# Sheet4.net
KiCad netlist of a schematic drawn in Altium Designer
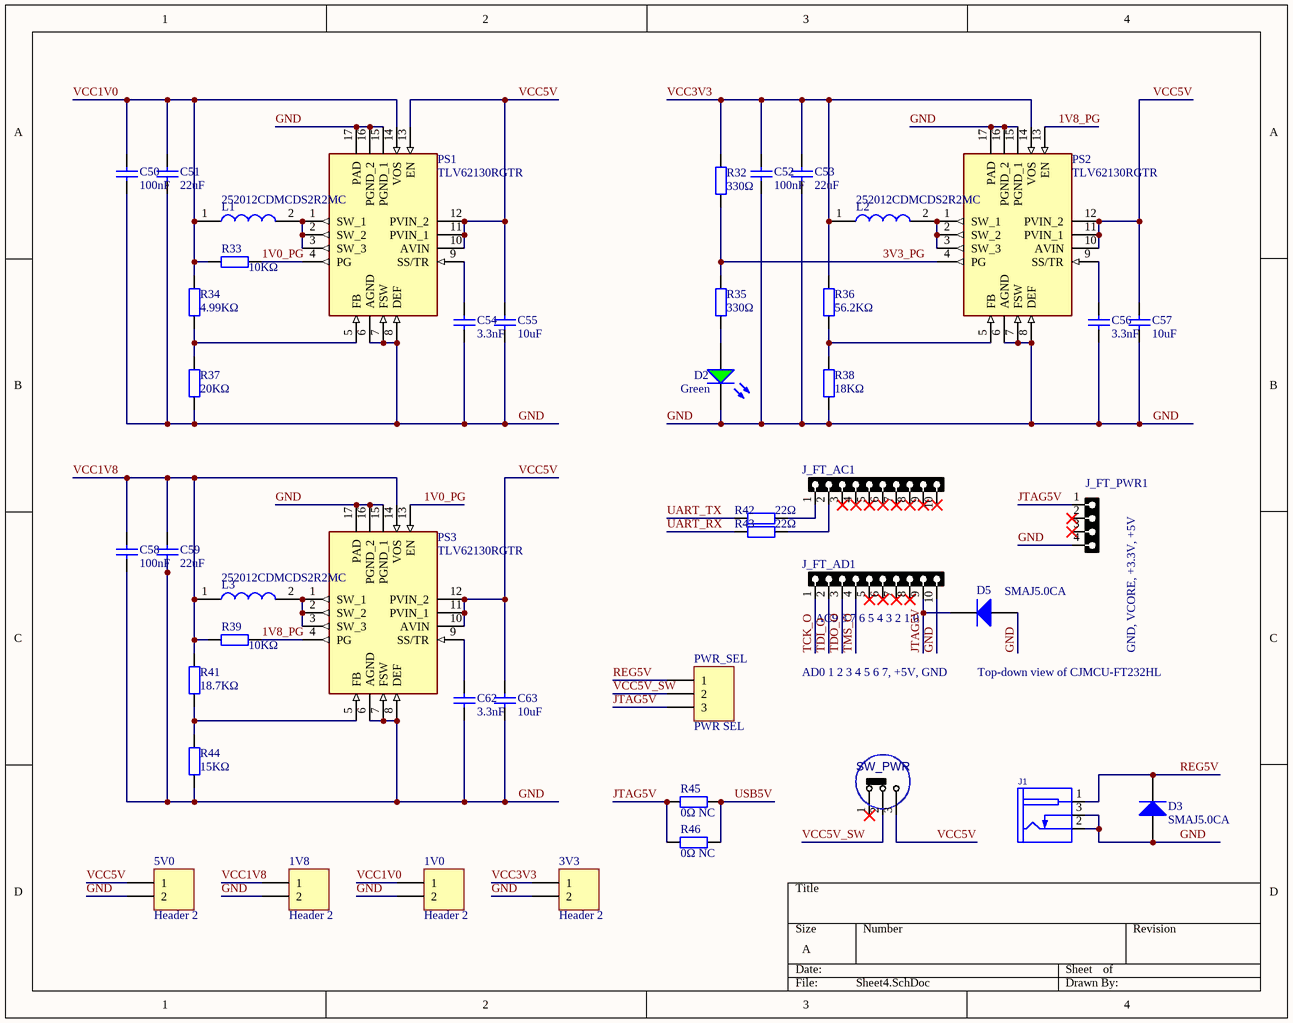
[diagram p0: Sheet4.SchDoc]

(export (version "E")
  (design (tool "Eeschema 10.0.6"))
  (components
    (comp (ref "1V0")
      (value "Header 2")
      (footprint "HDR1X2")
      (description "Header, 2-Pin")
      (fields (field (name "PUBLISHER") "Altium Limited"))
      (libsource (lib "Miscellaneous Connectors") (part "Header 2"))
    )
    (comp (ref "1V8")
      (value "Header 2")
      (footprint "HDR1X2")
      (description "Header, 2-Pin")
      (fields (field (name "PUBLISHER") "Altium Limited"))
      (libsource (lib "Miscellaneous Connectors") (part "Header 2"))
    )
    (comp (ref "3V3")
      (value "Header 2")
      (footprint "HDR1X2")
      (description "Header, 2-Pin")
      (fields (field (name "PUBLISHER") "Altium Limited"))
      (libsource (lib "Miscellaneous Connectors") (part "Header 2"))
    )
    (comp (ref "5V0")
      (value "Header 2")
      (footprint "HDR1X2")
      (description "Header, 2-Pin")
      (fields (field (name "PUBLISHER") "Altium Limited"))
      (libsource (lib "Miscellaneous Connectors") (part "Header 2"))
    )
    (comp (ref "C50")
      (value "100nF")
      (footprint "1206_C")
      (description "贴片电容")
      (libsource (lib "Cap") (part "1206 100nF (104) 10% 50V"))
    )
    (comp (ref "C51")
      (value "22uF")
      (footprint "0805_C")
      (description "贴片电容")
      (libsource (lib "Cap") (part "0805 22uF (226) 20% 25V"))
    )
    (comp (ref "C52")
      (value "100nF")
      (footprint "1206_C")
      (description "贴片电容")
      (libsource (lib "Cap") (part "1206 100nF (104) 10% 50V"))
    )
    (comp (ref "C53")
      (value "22uF")
      (footprint "0805_C")
      (description "贴片电容")
      (libsource (lib "Cap") (part "0805 22uF (226) 20% 25V"))
    )
    (comp (ref "C54")
      (value "3.3nF")
      (footprint "0805_C")
      (description "贴片电容")
      (libsource (lib "Cap") (part "0805 3.3nF (332) 10% 50V"))
    )
    (comp (ref "C55")
      (value "10uF")
      (footprint "1206_C")
      (description "贴片电容")
      (libsource (lib "Cap") (part "1206 10uF (106) 10% 50V"))
    )
    (comp (ref "C56")
      (value "3.3nF")
      (footprint "0805_C")
      (description "贴片电容")
      (libsource (lib "Cap") (part "0805 3.3nF (332) 10% 50V"))
    )
    (comp (ref "C57")
      (value "10uF")
      (footprint "1206_C")
      (description "贴片电容")
      (libsource (lib "Cap") (part "1206 10uF (106) 10% 50V"))
    )
    (comp (ref "C58")
      (value "100nF")
      (footprint "1206_C")
      (description "贴片电容")
      (libsource (lib "Cap") (part "1206 100nF (104) 10% 50V"))
    )
    (comp (ref "C59")
      (value "22uF")
      (footprint "0805_C")
      (description "贴片电容")
      (libsource (lib "Cap") (part "0805 22uF (226) 20% 25V"))
    )
    (comp (ref "C62")
      (value "3.3nF")
      (footprint "0805_C")
      (description "贴片电容")
      (libsource (lib "Cap") (part "0805 3.3nF (332) 10% 50V"))
    )
    (comp (ref "C63")
      (value "10uF")
      (footprint "1206_C")
      (description "贴片电容")
      (libsource (lib "Cap") (part "1206 10uF (106) 10% 50V"))
    )
    (comp (ref "D2")
      (value "Green")
      (footprint "0805_LED_S1")
      (description "发光二极管")
      (libsource (lib "LED") (part "0805 翠绿"))
    )
    (comp (ref "D3")
      (value "SMAJ5.0CA")
      (footprint "SMA(DO-214AC)_S1")
      (description "二极管 TVS")
      (libsource (lib "Diode") (part "SMA(DO-214AC) SS210"))
    )
    (comp (ref "D5")
      (value "SMAJ5.0CA")
      (footprint "SMA(DO-214AC)_S1")
      (description "二极管 TVS")
      (libsource (lib "Diode") (part "SMA(DO-214AC) SS210"))
    )
    (comp (ref "J1")
      (value "DC_POWER_JACK")
      (footprint "JAC_PWR2MM")
      (description "CONN, PWR JACK DC, PLUG DIAM 2.0MM RA THD")
      (fields
        (field (name "MANF") "CUI STACK")
        (field (name "MANF_P#") "PJ-202A, PJ-002AH, PJ-102AH, KLDX-0202")
      )
      (libsource (lib "Connector Power") (part "CONN_PWR_JACK2MM"))
    )
    (comp (ref "J_FT_AC1")
      (value "HDRF10")
      (footprint "HDR_F_1X10")
      (description "CONN, HEADER, Female, pitch: 2.54mm, 10POS")
      (libsource (lib "Connector Header 254") (part "HDR_F_1X10"))
    )
    (comp (ref "J_FT_AD1")
      (value "HDRF10")
      (footprint "HDR_F_1X10")
      (description "CONN, HEADER, Female, pitch: 2.54mm, 10POS")
      (libsource (lib "Connector Header 254") (part "HDR_F_1X10"))
    )
    (comp (ref "J_FT_PWR1")
      (value "HDRF4")
      (footprint "HDR_F_1X4")
      (description "CONN, HEADER, Female, pitch: 2.54mm, 4POS")
      (libsource (lib "Connector Header 254") (part "HDR_F_1X4"))
    )
    (comp (ref "L1")
      (value "252012CDMCDS2R2MC")
      (footprint "SamacSys:INDPM2520X120N")
      (description "Inductor")
      (fields (field (name "MANUFACTURER_PART_NUMBER") "252012CDMCDS‐2R2MC"))
      (libsource (lib "*") (part "252012CDMCDS2R2MC"))
    )
    (comp (ref "L2")
      (value "252012CDMCDS2R2MC")
      (footprint "SamacSys:INDPM2520X120N")
      (description "Inductor")
      (fields (field (name "MANUFACTURER_PART_NUMBER") "252012CDMCDS‐2R2MC"))
      (libsource (lib "*") (part "252012CDMCDS2R2MC"))
    )
    (comp (ref "L3")
      (value "252012CDMCDS2R2MC")
      (footprint "SamacSys:INDPM2520X120N")
      (description "Inductor")
      (fields (field (name "MANUFACTURER_PART_NUMBER") "252012CDMCDS‐2R2MC"))
      (libsource (lib "*") (part "252012CDMCDS2R2MC"))
    )
    (comp (ref "PS1")
      (value "TLV62130RGTR")
      (footprint "SamacSys:QFN50P300X300X100-17N-D")
      (description "Power Supply")
      (fields (field (name "MOUSER PART NUMBER") "595-TLV62130RGTR"))
      (libsource (lib "*") (part "TLV62130RGTR"))
    )
    (comp (ref "PS2")
      (value "TLV62130RGTR")
      (footprint "SamacSys:QFN50P300X300X100-17N-D")
      (description "Power Supply")
      (fields (field (name "MOUSER PART NUMBER") "595-TLV62130RGTR"))
      (libsource (lib "*") (part "TLV62130RGTR"))
    )
    (comp (ref "PS3")
      (value "TLV62130RGTR")
      (footprint "SamacSys:QFN50P300X300X100-17N-D")
      (description "Power Supply")
      (fields (field (name "MOUSER PART NUMBER") "595-TLV62130RGTR"))
      (libsource (lib "*") (part "TLV62130RGTR"))
    )
    (comp (ref "PWR_SEL")
      (value "PWR SEL")
      (footprint "HDR1X3")
      (description "Header, 3-Pin")
      (fields (field (name "PUBLISHER") "Altium Limited"))
      (libsource (lib "Miscellaneous Connectors") (part "Header 3"))
    )
    (comp (ref "R32")
      (value "330Ω")
      (footprint "0805_R")
      (description "贴片电阻")
      (libsource (lib "RES") (part "0805 330Ω (3300) 1%"))
    )
    (comp (ref "R33")
      (value "10KΩ")
      (footprint "1206_R")
      (description "贴片电阻")
      (libsource (lib "RES") (part "1206 10KΩ (1002) 1%"))
    )
    (comp (ref "R34")
      (value "4.99KΩ")
      (footprint "0805_R")
      (description "贴片电阻")
      (libsource (lib "RES") (part "0805 4.99KΩ (4991) 1%"))
    )
    (comp (ref "R35")
      (value "330Ω")
      (footprint "0805_R")
      (description "贴片电阻")
      (libsource (lib "RES") (part "0805 330Ω (3300) 1%"))
    )
    (comp (ref "R36")
      (value "56.2KΩ")
      (footprint "0805_R")
      (description "贴片电阻 56.2k")
      (libsource (lib "RES") (part "0805 56KΩ (5602) 1%"))
    )
    (comp (ref "R37")
      (value "20KΩ")
      (footprint "0805_R")
      (description "贴片电阻")
      (libsource (lib "RES") (part "0805 20KΩ (2002) 1%"))
    )
    (comp (ref "R38")
      (value "18KΩ")
      (footprint "0805_R")
      (description "贴片电阻")
      (libsource (lib "RES") (part "0805 18KΩ (1802) 1%"))
    )
    (comp (ref "R39")
      (value "10KΩ")
      (footprint "1206_R")
      (description "贴片电阻")
      (libsource (lib "RES") (part "1206 10KΩ (1002) 1%"))
    )
    (comp (ref "R41")
      (value "18.7KΩ")
      (footprint "0805_R")
      (description "贴片电阻 18.7k")
      (libsource (lib "RES") (part "0805 18KΩ (1802) 1%"))
    )
    (comp (ref "R42")
      (value "22Ω")
      (footprint "1206_R")
      (description "贴片电阻")
      (libsource (lib "RES") (part "1206 22Ω (22R0) 1%"))
    )
    (comp (ref "R43")
      (value "22Ω")
      (footprint "1206_R")
      (description "贴片电阻")
      (libsource (lib "RES") (part "1206 22Ω (22R0) 1%"))
    )
    (comp (ref "R44")
      (value "15KΩ")
      (footprint "0805_R")
      (description "贴片电阻")
      (libsource (lib "RES") (part "0805 15KΩ (1502) 1%"))
    )
    (comp (ref "R45")
      (value "0Ω NC")
      (footprint "0805_R")
      (description "贴片电阻")
      (libsource (lib "RES") (part "0805 0Ω (0R0) 1%"))
    )
    (comp (ref "R46")
      (value "0Ω NC")
      (footprint "0805_R")
      (description "贴片电阻")
      (libsource (lib "RES") (part "0805 0Ω (0R0) 1%"))
    )
    (comp (ref "SW_PWR")
      (value "SlideSwitch")
      (footprint "SWSLIDT_SPDT_S_8X4")
      (description "SWITCH, SLIDE, SPDT, 8.6X4.3mm, THD")
      (fields (field (name "MANF") "C&K") (field (name "MANF_PART#") "OS102011MS2QN1"))
      (libsource (lib "Switch Slide") (part "SWSLIDT_SPDT_S_8X4"))
    )
  )
  (nets
    (net (code "1") (name "/1V0_PG") (class "Default")
      (node (ref "PS1") (pin "4") (pinfunction "PG_4") (pintype "output"))
      (node (ref "PS3") (pin "13") (pinfunction "EN_13") (pintype "input"))
      (node (ref "R33") (pin "2") (pinfunction "2_2") (pintype "passive"))
    )
    (net (code "2") (name "/1V8_PG") (class "Default")
      (node (ref "PS2") (pin "13") (pinfunction "EN_13") (pintype "input"))
      (node (ref "PS3") (pin "4") (pinfunction "PG_4") (pintype "output"))
      (node (ref "R39") (pin "2") (pinfunction "2_2") (pintype "passive"))
    )
    (net (code "3") (name "/3V3_PG") (class "Default")
      (node (ref "PS2") (pin "4") (pinfunction "PG_4") (pintype "output"))
      (node (ref "R32") (pin "1") (pinfunction "1_1") (pintype "passive"))
      (node (ref "R35") (pin "2") (pinfunction "2_2") (pintype "passive"))
    )
    (net (code "4") (name "/GND") (class "Default")
      (node (ref "1V0") (pin "2") (pinfunction "2_2") (pintype "passive"))
      (node (ref "1V8") (pin "2") (pinfunction "2_2") (pintype "passive"))
      (node (ref "3V3") (pin "2") (pinfunction "2_2") (pintype "passive"))
      (node (ref "5V0") (pin "2") (pinfunction "2_2") (pintype "passive"))
      (node (ref "C50") (pin "1") (pinfunction "1_1") (pintype "passive"))
      (node (ref "C51") (pin "1") (pinfunction "1_1") (pintype "passive"))
      (node (ref "C52") (pin "1") (pinfunction "1_1") (pintype "passive"))
      (node (ref "C53") (pin "1") (pinfunction "1_1") (pintype "passive"))
      (node (ref "C54") (pin "1") (pinfunction "1_1") (pintype "passive"))
      (node (ref "C55") (pin "1") (pinfunction "1_1") (pintype "passive"))
      (node (ref "C56") (pin "1") (pinfunction "1_1") (pintype "passive"))
      (node (ref "C57") (pin "1") (pinfunction "1_1") (pintype "passive"))
      (node (ref "C58") (pin "1") (pinfunction "1_1") (pintype "passive"))
      (node (ref "C59") (pin "1") (pinfunction "1_1") (pintype "passive"))
      (node (ref "C62") (pin "1") (pinfunction "1_1") (pintype "passive"))
      (node (ref "C63") (pin "1") (pinfunction "1_1") (pintype "passive"))
      (node (ref "D2") (pin "K") (pinfunction "K_K") (pintype "passive"))
      (node (ref "D3") (pin "1") (pinfunction "A_1") (pintype "passive"))
      (node (ref "D5") (pin "1") (pinfunction "A_1") (pintype "passive"))
      (node (ref "J1") (pin "2") (pinfunction "SLEEVE_2") (pintype "power_in"))
      (node (ref "J1") (pin "3") (pinfunction "INSERTION_DET_3") (pintype "power_in"))
      (node (ref "J_FT_AD1") (pin "10") (pinfunction "10_10") (pintype "passive"))
      (node (ref "J_FT_PWR1") (pin "4") (pinfunction "4_4") (pintype "passive"))
      (node (ref "PS1") (pin "15") (pinfunction "PGND_1_15") (pintype "power_in"))
      (node (ref "PS1") (pin "16") (pinfunction "PGND_2_16") (pintype "power_in"))
      (node (ref "PS1") (pin "17") (pinfunction "PAD_17") (pintype "power_in"))
      (node (ref "PS1") (pin "6") (pinfunction "AGND_6") (pintype "power_in"))
      (node (ref "PS1") (pin "7") (pinfunction "FSW_7") (pintype "input"))
      (node (ref "PS1") (pin "8") (pinfunction "DEF_8") (pintype "input"))
      (node (ref "PS2") (pin "15") (pinfunction "PGND_1_15") (pintype "power_in"))
      (node (ref "PS2") (pin "16") (pinfunction "PGND_2_16") (pintype "power_in"))
      (node (ref "PS2") (pin "17") (pinfunction "PAD_17") (pintype "power_in"))
      (node (ref "PS2") (pin "6") (pinfunction "AGND_6") (pintype "power_in"))
      (node (ref "PS2") (pin "7") (pinfunction "FSW_7") (pintype "input"))
      (node (ref "PS2") (pin "8") (pinfunction "DEF_8") (pintype "input"))
      (node (ref "PS3") (pin "15") (pinfunction "PGND_1_15") (pintype "power_in"))
      (node (ref "PS3") (pin "16") (pinfunction "PGND_2_16") (pintype "power_in"))
      (node (ref "PS3") (pin "17") (pinfunction "PAD_17") (pintype "power_in"))
      (node (ref "PS3") (pin "6") (pinfunction "AGND_6") (pintype "power_in"))
      (node (ref "PS3") (pin "7") (pinfunction "FSW_7") (pintype "input"))
      (node (ref "PS3") (pin "8") (pinfunction "DEF_8") (pintype "input"))
      (node (ref "R37") (pin "1") (pinfunction "1_1") (pintype "passive"))
      (node (ref "R38") (pin "1") (pinfunction "1_1") (pintype "passive"))
      (node (ref "R44") (pin "1") (pinfunction "1_1") (pintype "passive"))
    )
    (net (code "5") (name "/JTAG5V") (class "Default")
      (node (ref "D5") (pin "2") (pinfunction "K_2") (pintype "passive"))
      (node (ref "J_FT_AD1") (pin "9") (pinfunction "9_9") (pintype "passive"))
      (node (ref "J_FT_PWR1") (pin "1") (pinfunction "1_1") (pintype "passive"))
      (node (ref "PWR_SEL") (pin "3") (pinfunction "3_3") (pintype "passive"))
      (node (ref "R45") (pin "1") (pinfunction "1_1") (pintype "passive"))
      (node (ref "R46") (pin "1") (pinfunction "1_1") (pintype "passive"))
    )
    (net (code "6") (name "/REG5V") (class "Default")
      (node (ref "D3") (pin "2") (pinfunction "K_2") (pintype "passive"))
      (node (ref "J1") (pin "1") (pinfunction "TIP_1") (pintype "power_in"))
      (node (ref "PWR_SEL") (pin "1") (pinfunction "1_1") (pintype "passive"))
    )
    (net (code "7") (name "/TCK_O") (class "Default")
      (node (ref "J_FT_AD1") (pin "1") (pinfunction "1_1") (pintype "passive"))
    )
    (net (code "8") (name "/TDI_O") (class "Default")
      (node (ref "J_FT_AD1") (pin "2") (pinfunction "2_2") (pintype "passive"))
    )
    (net (code "9") (name "/TDO_O") (class "Default")
      (node (ref "J_FT_AD1") (pin "3") (pinfunction "3_3") (pintype "passive"))
    )
    (net (code "10") (name "/TMS_O") (class "Default")
      (node (ref "J_FT_AD1") (pin "4") (pinfunction "4_4") (pintype "passive"))
    )
    (net (code "11") (name "/UART_RX") (class "Default")
      (node (ref "R43") (pin "1") (pinfunction "1_1") (pintype "passive"))
    )
    (net (code "12") (name "/UART_TX") (class "Default")
      (node (ref "R42") (pin "1") (pinfunction "1_1") (pintype "passive"))
    )
    (net (code "13") (name "/USB5V") (class "Default")
      (node (ref "R45") (pin "2") (pinfunction "2_2") (pintype "passive"))
      (node (ref "R46") (pin "2") (pinfunction "2_2") (pintype "passive"))
    )
    (net (code "14") (name "/VCC1V0") (class "Default")
      (node (ref "1V0") (pin "1") (pinfunction "1_1") (pintype "passive"))
      (node (ref "C50") (pin "2") (pinfunction "2_2") (pintype "passive"))
      (node (ref "C51") (pin "2") (pinfunction "2_2") (pintype "passive"))
      (node (ref "L1") (pin "1") (pinfunction "1_1") (pintype "passive"))
      (node (ref "PS1") (pin "14") (pinfunction "VOS_14") (pintype "input"))
      (node (ref "R33") (pin "1") (pinfunction "1_1") (pintype "passive"))
      (node (ref "R34") (pin "2") (pinfunction "2_2") (pintype "passive"))
    )
    (net (code "15") (name "/VCC1V8") (class "Default")
      (node (ref "1V8") (pin "1") (pinfunction "1_1") (pintype "passive"))
      (node (ref "C58") (pin "2") (pinfunction "2_2") (pintype "passive"))
      (node (ref "C59") (pin "2") (pinfunction "2_2") (pintype "passive"))
      (node (ref "L3") (pin "1") (pinfunction "1_1") (pintype "passive"))
      (node (ref "PS3") (pin "14") (pinfunction "VOS_14") (pintype "input"))
      (node (ref "R39") (pin "1") (pinfunction "1_1") (pintype "passive"))
      (node (ref "R41") (pin "2") (pinfunction "2_2") (pintype "passive"))
    )
    (net (code "16") (name "/VCC3V3") (class "Default")
      (node (ref "3V3") (pin "1") (pinfunction "1_1") (pintype "passive"))
      (node (ref "C52") (pin "2") (pinfunction "2_2") (pintype "passive"))
      (node (ref "C53") (pin "2") (pinfunction "2_2") (pintype "passive"))
      (node (ref "L2") (pin "1") (pinfunction "1_1") (pintype "passive"))
      (node (ref "PS2") (pin "14") (pinfunction "VOS_14") (pintype "input"))
      (node (ref "R32") (pin "2") (pinfunction "2_2") (pintype "passive"))
      (node (ref "R36") (pin "2") (pinfunction "2_2") (pintype "passive"))
    )
    (net (code "17") (name "/VCC5V") (class "Default")
      (node (ref "5V0") (pin "1") (pinfunction "1_1") (pintype "passive"))
      (node (ref "C55") (pin "2") (pinfunction "2_2") (pintype "passive"))
      (node (ref "C57") (pin "2") (pinfunction "2_2") (pintype "passive"))
      (node (ref "C63") (pin "2") (pinfunction "2_2") (pintype "passive"))
      (node (ref "PS1") (pin "10") (pinfunction "AVIN_10") (pintype "power_in"))
      (node (ref "PS1") (pin "11") (pinfunction "PVIN_1_11") (pintype "power_in"))
      (node (ref "PS1") (pin "12") (pinfunction "PVIN_2_12") (pintype "power_in"))
      (node (ref "PS1") (pin "13") (pinfunction "EN_13") (pintype "input"))
      (node (ref "PS2") (pin "10") (pinfunction "AVIN_10") (pintype "power_in"))
      (node (ref "PS2") (pin "11") (pinfunction "PVIN_1_11") (pintype "power_in"))
      (node (ref "PS2") (pin "12") (pinfunction "PVIN_2_12") (pintype "power_in"))
      (node (ref "PS3") (pin "10") (pinfunction "AVIN_10") (pintype "power_in"))
      (node (ref "PS3") (pin "11") (pinfunction "PVIN_1_11") (pintype "power_in"))
      (node (ref "PS3") (pin "12") (pinfunction "PVIN_2_12") (pintype "power_in"))
      (node (ref "SW_PWR") (pin "3") (pinfunction "P4_3") (pintype "passive"))
    )
    (net (code "18") (name "/VCC5V_SW") (class "Default")
      (node (ref "PWR_SEL") (pin "2") (pinfunction "2_2") (pintype "passive"))
      (node (ref "SW_PWR") (pin "2") (pinfunction "P3_2") (pintype "passive"))
    )
    (net (code "19") (name "Net-(D2-PadA)") (class "Default")
      (node (ref "D2") (pin "A") (pinfunction "A_A") (pintype "passive"))
      (node (ref "R35") (pin "1") (pinfunction "1_1") (pintype "passive"))
    )
    (net (code "20") (name "Net-(J_FT_AC1-Pad1)") (class "Default")
      (node (ref "J_FT_AC1") (pin "1") (pinfunction "1_1") (pintype "passive"))
      (node (ref "R42") (pin "2") (pinfunction "2_2") (pintype "passive"))
    )
    (net (code "21") (name "Net-(J_FT_AC1-Pad2)") (class "Default")
      (node (ref "J_FT_AC1") (pin "2") (pinfunction "2_2") (pintype "passive"))
      (node (ref "R43") (pin "2") (pinfunction "2_2") (pintype "passive"))
    )
    (net (code "22") (name "Net-(PS1-FB)") (class "Default")
      (node (ref "PS1") (pin "5") (pinfunction "FB_5") (pintype "input"))
      (node (ref "R34") (pin "1") (pinfunction "1_1") (pintype "passive"))
      (node (ref "R37") (pin "2") (pinfunction "2_2") (pintype "passive"))
    )
    (net (code "23") (name "Net-(PS1-SS{slash}TR)") (class "Default")
      (node (ref "C54") (pin "2") (pinfunction "2_2") (pintype "passive"))
      (node (ref "PS1") (pin "9") (pinfunction "SS/TR_9") (pintype "input"))
    )
    (net (code "24") (name "Net-(PS1-SW_1)") (class "Default")
      (node (ref "L1") (pin "2") (pinfunction "2_2") (pintype "passive"))
      (node (ref "PS1") (pin "1") (pinfunction "SW_1_1") (pintype "output"))
      (node (ref "PS1") (pin "2") (pinfunction "SW_2_2") (pintype "output"))
      (node (ref "PS1") (pin "3") (pinfunction "SW_3_3") (pintype "output"))
    )
    (net (code "25") (name "Net-(PS2-FB)") (class "Default")
      (node (ref "PS2") (pin "5") (pinfunction "FB_5") (pintype "input"))
      (node (ref "R36") (pin "1") (pinfunction "1_1") (pintype "passive"))
      (node (ref "R38") (pin "2") (pinfunction "2_2") (pintype "passive"))
    )
    (net (code "26") (name "Net-(PS2-SS{slash}TR)") (class "Default")
      (node (ref "C56") (pin "2") (pinfunction "2_2") (pintype "passive"))
      (node (ref "PS2") (pin "9") (pinfunction "SS/TR_9") (pintype "input"))
    )
    (net (code "27") (name "Net-(PS2-SW_1)") (class "Default")
      (node (ref "L2") (pin "2") (pinfunction "2_2") (pintype "passive"))
      (node (ref "PS2") (pin "1") (pinfunction "SW_1_1") (pintype "output"))
      (node (ref "PS2") (pin "2") (pinfunction "SW_2_2") (pintype "output"))
      (node (ref "PS2") (pin "3") (pinfunction "SW_3_3") (pintype "output"))
    )
    (net (code "28") (name "Net-(PS3-FB)") (class "Default")
      (node (ref "PS3") (pin "5") (pinfunction "FB_5") (pintype "input"))
      (node (ref "R41") (pin "1") (pinfunction "1_1") (pintype "passive"))
      (node (ref "R44") (pin "2") (pinfunction "2_2") (pintype "passive"))
    )
    (net (code "29") (name "Net-(PS3-SS{slash}TR)") (class "Default")
      (node (ref "C62") (pin "2") (pinfunction "2_2") (pintype "passive"))
      (node (ref "PS3") (pin "9") (pinfunction "SS/TR_9") (pintype "input"))
    )
    (net (code "30") (name "Net-(PS3-SW_1)") (class "Default")
      (node (ref "L3") (pin "2") (pinfunction "2_2") (pintype "passive"))
      (node (ref "PS3") (pin "1") (pinfunction "SW_1_1") (pintype "output"))
      (node (ref "PS3") (pin "2") (pinfunction "SW_2_2") (pintype "output"))
      (node (ref "PS3") (pin "3") (pinfunction "SW_3_3") (pintype "output"))
    )
    (net (code "31") (name "unconnected-(J_FT_AC1-Pad3)") (class "Default")
      (node (ref "J_FT_AC1") (pin "3") (pinfunction "3_3") (pintype "passive+no_connect"))
    )
    (net (code "32") (name "unconnected-(J_FT_AC1-Pad4)") (class "Default")
      (node (ref "J_FT_AC1") (pin "4") (pinfunction "4_4") (pintype "passive+no_connect"))
    )
    (net (code "33") (name "unconnected-(J_FT_AC1-Pad5)") (class "Default")
      (node (ref "J_FT_AC1") (pin "5") (pinfunction "5_5") (pintype "passive+no_connect"))
    )
    (net (code "34") (name "unconnected-(J_FT_AC1-Pad6)") (class "Default")
      (node (ref "J_FT_AC1") (pin "6") (pinfunction "6_6") (pintype "passive+no_connect"))
    )
    (net (code "35") (name "unconnected-(J_FT_AC1-Pad7)") (class "Default")
      (node (ref "J_FT_AC1") (pin "7") (pinfunction "7_7") (pintype "passive+no_connect"))
    )
    (net (code "36") (name "unconnected-(J_FT_AC1-Pad8)") (class "Default")
      (node (ref "J_FT_AC1") (pin "8") (pinfunction "8_8") (pintype "passive+no_connect"))
    )
    (net (code "37") (name "unconnected-(J_FT_AC1-Pad9)") (class "Default")
      (node (ref "J_FT_AC1") (pin "9") (pinfunction "9_9") (pintype "passive+no_connect"))
    )
    (net (code "38") (name "unconnected-(J_FT_AC1-Pad10)") (class "Default")
      (node (ref "J_FT_AC1") (pin "10") (pinfunction "10_10") (pintype "passive+no_connect"))
    )
    (net (code "39") (name "unconnected-(J_FT_AD1-Pad5)") (class "Default")
      (node (ref "J_FT_AD1") (pin "5") (pinfunction "5_5") (pintype "passive+no_connect"))
    )
    (net (code "40") (name "unconnected-(J_FT_AD1-Pad6)") (class "Default")
      (node (ref "J_FT_AD1") (pin "6") (pinfunction "6_6") (pintype "passive+no_connect"))
    )
    (net (code "41") (name "unconnected-(J_FT_AD1-Pad7)") (class "Default")
      (node (ref "J_FT_AD1") (pin "7") (pinfunction "7_7") (pintype "passive+no_connect"))
    )
    (net (code "42") (name "unconnected-(J_FT_AD1-Pad8)") (class "Default")
      (node (ref "J_FT_AD1") (pin "8") (pinfunction "8_8") (pintype "passive+no_connect"))
    )
    (net (code "43") (name "unconnected-(J_FT_PWR1-Pad2)") (class "Default")
      (node (ref "J_FT_PWR1") (pin "2") (pinfunction "2_2") (pintype "passive+no_connect"))
    )
    (net (code "44") (name "unconnected-(J_FT_PWR1-Pad3)") (class "Default")
      (node (ref "J_FT_PWR1") (pin "3") (pinfunction "3_3") (pintype "passive+no_connect"))
    )
    (net (code "45") (name "unconnected-(SW_PWR-P1-Pad1)") (class "Default")
      (node (ref "SW_PWR") (pin "1") (pinfunction "P1_1") (pintype "passive+no_connect"))
    )
  )
)
